# schematic.net
KiCad netlist of a schematic drawn in Altium Designer
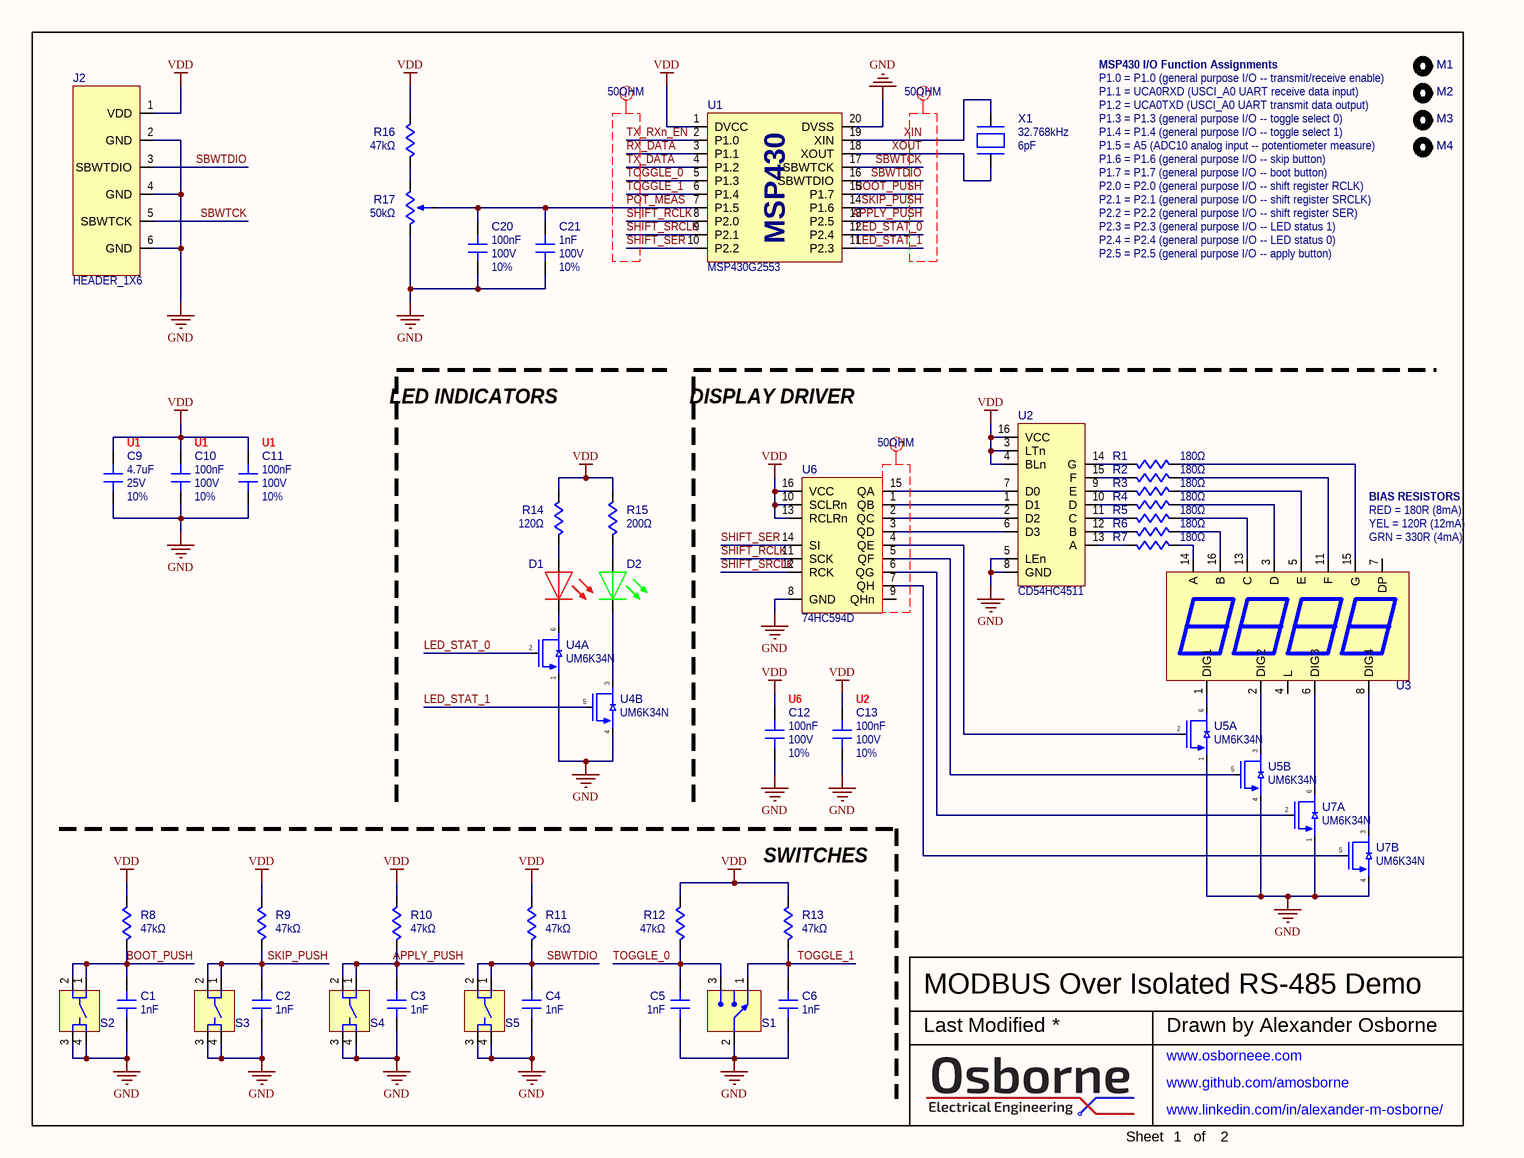
[diagram p0: schematic.SchDoc]

(export (version "E")
  (design (tool "Eeschema 10.0.6"))
  (components
    (comp (ref "C1")
      (value "1nF")
      (footprint "C0805")
      (description "CAP, CER, 1nF ±10%, 100V, 0805")
      (fields (field (name "VOLTAGE") "100V") (field (name "TOLERANCE") "10%"))
      (libsource (lib "schematic_library") (part "CAP-CER-1N00-10T-100V-0805"))
    )
    (comp (ref "C2")
      (value "1nF")
      (footprint "C0805")
      (description "CAP, CER, 1nF ±10%, 100V, 0805")
      (fields (field (name "VOLTAGE") "100V") (field (name "TOLERANCE") "10%"))
      (libsource (lib "schematic_library") (part "CAP-CER-1N00-10T-100V-0805"))
    )
    (comp (ref "C3")
      (value "1nF")
      (footprint "C0805")
      (description "CAP, CER, 1nF ±10%, 100V, 0805")
      (fields (field (name "VOLTAGE") "100V") (field (name "TOLERANCE") "10%"))
      (libsource (lib "schematic_library") (part "CAP-CER-1N00-10T-100V-0805"))
    )
    (comp (ref "C4")
      (value "1nF")
      (footprint "C0805")
      (description "CAP, CER, 1nF ±10%, 100V, 0805")
      (fields (field (name "VOLTAGE") "100V") (field (name "TOLERANCE") "10%"))
      (libsource (lib "schematic_library") (part "CAP-CER-1N00-10T-100V-0805"))
    )
    (comp (ref "C5")
      (value "1nF")
      (footprint "C0805")
      (description "CAP, CER, 1nF ±10%, 100V, 0805")
      (fields (field (name "VOLTAGE") "100V") (field (name "TOLERANCE") "10%"))
      (libsource (lib "schematic_library") (part "CAP-CER-1N00-10T-100V-0805"))
    )
    (comp (ref "C6")
      (value "1nF")
      (footprint "C0805")
      (description "CAP, CER, 1nF ±10%, 100V, 0805")
      (fields (field (name "VOLTAGE") "100V") (field (name "TOLERANCE") "10%"))
      (libsource (lib "schematic_library") (part "CAP-CER-1N00-10T-100V-0805"))
    )
    (comp (ref "C9")
      (value "4.7uF")
      (footprint "C0805")
      (description "CAP, CER, 4.7uF ±10%, 25V, 0805")
      (fields
        (field (name "VOLTAGE") "25V")
        (field (name "TOLERANCE") "10%")
        (field (name "Comment") "CAP-CER-4U70-10T-25V-0805")
      )
      (libsource (lib "schematic_library") (part "CAP-CER-4U70-10T-25V-0805"))
    )
    (comp (ref "C10")
      (value "100nF")
      (footprint "C0805")
      (description "CAP, CER, 100nF ±10%, 100V, 0805")
      (fields
        (field (name "VOLTAGE") "100V")
        (field (name "TOLERANCE") "10%")
        (field (name "Comment") "CAP-CER-100N-10T-100V-0805")
      )
      (libsource (lib "schematic_library") (part "CAP-CER-100N-10T-100V-0805"))
    )
    (comp (ref "C11")
      (value "100nF")
      (footprint "C0805")
      (description "CAP, CER, 100nF ±10%, 100V, 0805")
      (fields
        (field (name "VOLTAGE") "100V")
        (field (name "TOLERANCE") "10%")
        (field (name "Comment") "CAP-CER-100N-10T-100V-0805")
      )
      (libsource (lib "schematic_library") (part "CAP-CER-100N-10T-100V-0805"))
    )
    (comp (ref "C12")
      (value "100nF")
      (footprint "C0805")
      (description "CAP, CER, 100nF ±10%, 100V, 0805")
      (fields
        (field (name "VOLTAGE") "100V")
        (field (name "TOLERANCE") "10%")
        (field (name "Comment") "CAP-CER-100N-10T-100V-0805")
      )
      (libsource (lib "schematic_library") (part "CAP-CER-100N-10T-100V-0805"))
    )
    (comp (ref "C13")
      (value "100nF")
      (footprint "C0805")
      (description "CAP, CER, 100nF ±10%, 100V, 0805")
      (fields
        (field (name "VOLTAGE") "100V")
        (field (name "TOLERANCE") "10%")
        (field (name "Comment") "CAP-CER-100N-10T-100V-0805")
      )
      (libsource (lib "schematic_library") (part "CAP-CER-100N-10T-100V-0805"))
    )
    (comp (ref "C20")
      (value "100nF")
      (footprint "C0805")
      (description "CAP, CER, 100nF ±10%, 100V, 0805")
      (fields
        (field (name "VOLTAGE") "100V")
        (field (name "TOLERANCE") "10%")
        (field (name "Comment") "CAP-CER-100N-10T-100V-0805")
      )
      (libsource (lib "schematic_library") (part "CAP-CER-100N-10T-100V-0805"))
    )
    (comp (ref "C21")
      (value "1nF")
      (footprint "C0805")
      (description "CAP, CER, 1nF ±10%, 100V, 0805")
      (fields
        (field (name "VOLTAGE") "100V")
        (field (name "TOLERANCE") "10%")
        (field (name "Comment") "CAP-CER-1N00-10T-100V-0805")
      )
      (libsource (lib "schematic_library") (part "CAP-CER-1N00-10T-100V-0805"))
    )
    (comp (ref "D1")
      (value "LED_RED")
      (footprint "D0805")
      (description "Red LED Indicator 0805")
      (libsource (lib "schematic_library") (part "LED_RED"))
    )
    (comp (ref "D2")
      (value "LED_GREEN")
      (footprint "D0805")
      (description "Green LED Indicator 0805")
      (libsource (lib "schematic_library") (part "LED_GREEN"))
    )
    (comp (ref "J2")
      (value "HEADER_1X6")
      (footprint "Header_1x6")
      (description "Header, 1-Row, 6-Position")
      (libsource (lib "schematic_library") (part "HEADER_1X6"))
    )
    (comp (ref "M1")
      (value "MTG_HOLE")
      (footprint "MTG_HOLE_No4")
      (description "Mounting Hole")
      (libsource (lib "schematic_library") (part "MTG_HOLE"))
    )
    (comp (ref "M2")
      (value "MTG_HOLE")
      (footprint "MTG_HOLE_No4")
      (description "Mounting Hole")
      (libsource (lib "schematic_library") (part "MTG_HOLE"))
    )
    (comp (ref "M3")
      (value "MTG_HOLE")
      (footprint "MTG_HOLE_No4")
      (description "Mounting Hole")
      (libsource (lib "schematic_library") (part "MTG_HOLE"))
    )
    (comp (ref "M4")
      (value "MTG_HOLE")
      (footprint "MTG_HOLE_No4")
      (description "Mounting Hole")
      (libsource (lib "schematic_library") (part "MTG_HOLE"))
    )
    (comp (ref "R1")
      (value "180Ω")
      (footprint "R0805")
      (description "RES, 180Ω ±1.00%, 125mW, 0805")
      (fields (field (name "TOLERANCE") "1%") (field (name "POWER") "125mW"))
      (libsource (lib "schematic_library") (part "RES-180R-1T00-W125-0805"))
    )
    (comp (ref "R2")
      (value "180Ω")
      (footprint "R0805")
      (description "RES, 180Ω ±1.00%, 125mW, 0805")
      (fields (field (name "TOLERANCE") "1%") (field (name "POWER") "125mW"))
      (libsource (lib "schematic_library") (part "RES-180R-1T00-W125-0805"))
    )
    (comp (ref "R3")
      (value "180Ω")
      (footprint "R0805")
      (description "RES, 180Ω ±1.00%, 125mW, 0805")
      (fields (field (name "TOLERANCE") "1%") (field (name "POWER") "125mW"))
      (libsource (lib "schematic_library") (part "RES-180R-1T00-W125-0805"))
    )
    (comp (ref "R4")
      (value "180Ω")
      (footprint "R0805")
      (description "RES, 180Ω ±1.00%, 125mW, 0805")
      (fields (field (name "TOLERANCE") "1%") (field (name "POWER") "125mW"))
      (libsource (lib "schematic_library") (part "RES-180R-1T00-W125-0805"))
    )
    (comp (ref "R5")
      (value "180Ω")
      (footprint "R0805")
      (description "RES, 180Ω ±1.00%, 125mW, 0805")
      (fields (field (name "TOLERANCE") "1%") (field (name "POWER") "125mW"))
      (libsource (lib "schematic_library") (part "RES-180R-1T00-W125-0805"))
    )
    (comp (ref "R6")
      (value "180Ω")
      (footprint "R0805")
      (description "RES, 180Ω ±1.00%, 125mW, 0805")
      (fields (field (name "TOLERANCE") "1%") (field (name "POWER") "125mW"))
      (libsource (lib "schematic_library") (part "RES-180R-1T00-W125-0805"))
    )
    (comp (ref "R7")
      (value "180Ω")
      (footprint "R0805")
      (description "RES, 180Ω ±1.00%, 125mW, 0805")
      (fields (field (name "TOLERANCE") "1%") (field (name "POWER") "125mW"))
      (libsource (lib "schematic_library") (part "RES-180R-1T00-W125-0805"))
    )
    (comp (ref "R8")
      (value "47kΩ")
      (footprint "R0805")
      (description "RES, 47.0kΩ ±1.00%, 125mW, 0805")
      (fields (field (name "TOLERANCE") "1%") (field (name "POWER") "125mW"))
      (libsource (lib "schematic_library") (part "RES-47K0-1T00-W125-0805"))
    )
    (comp (ref "R9")
      (value "47kΩ")
      (footprint "R0805")
      (description "RES, 47.0kΩ ±1.00%, 125mW, 0805")
      (fields (field (name "TOLERANCE") "1%") (field (name "POWER") "125mW"))
      (libsource (lib "schematic_library") (part "RES-47K0-1T00-W125-0805"))
    )
    (comp (ref "R10")
      (value "47kΩ")
      (footprint "R0805")
      (description "RES, 47.0kΩ ±1.00%, 125mW, 0805")
      (fields (field (name "TOLERANCE") "1%") (field (name "POWER") "125mW"))
      (libsource (lib "schematic_library") (part "RES-47K0-1T00-W125-0805"))
    )
    (comp (ref "R11")
      (value "47kΩ")
      (footprint "R0805")
      (description "RES, 47.0kΩ ±1.00%, 125mW, 0805")
      (fields (field (name "TOLERANCE") "1%") (field (name "POWER") "125mW"))
      (libsource (lib "schematic_library") (part "RES-47K0-1T00-W125-0805"))
    )
    (comp (ref "R12")
      (value "47kΩ")
      (footprint "R0805")
      (description "RES, 47.0kΩ ±1.00%, 125mW, 0805")
      (fields (field (name "TOLERANCE") "1%") (field (name "POWER") "125mW"))
      (libsource (lib "schematic_library") (part "RES-47K0-1T00-W125-0805"))
    )
    (comp (ref "R13")
      (value "47kΩ")
      (footprint "R0805")
      (description "RES, 47.0kΩ ±1.00%, 125mW, 0805")
      (fields (field (name "TOLERANCE") "1%") (field (name "POWER") "125mW"))
      (libsource (lib "schematic_library") (part "RES-47K0-1T00-W125-0805"))
    )
    (comp (ref "R14")
      (value "120Ω")
      (footprint "R0805")
      (description "RES, 120Ω ±1.00%, 125mW, 0805")
      (fields (field (name "TOLERANCE") "1%") (field (name "POWER") "125mW"))
      (libsource (lib "schematic_library") (part "RES-120R-1T00-W125-0805"))
    )
    (comp (ref "R15")
      (value "200Ω")
      (footprint "R0805")
      (description "RES, 200Ω ±1.00%, 125mW, 0805")
      (fields (field (name "TOLERANCE") "1%") (field (name "POWER") "125mW"))
      (libsource (lib "schematic_library") (part "RES-200R-1T00-W125-0805"))
    )
    (comp (ref "R16")
      (value "47kΩ")
      (footprint "R0805")
      (description "RES, 47.0kΩ ±1.00%, 125mW, 0805")
      (fields (field (name "TOLERANCE") "1%") (field (name "POWER") "125mW"))
      (libsource (lib "schematic_library") (part "RES-47K0-1T00-W125-0805"))
    )
    (comp (ref "R17")
      (value "50kΩ")
      (footprint "3352T_Trimpot")
      (description "50kOhm Thumbwheel Potentiometer")
      (fields (field (name "Comment") "RES-50K0-TRIMMER"))
      (libsource (lib "schematic_library") (part "RES-50K0-TRIMMER"))
    )
    (comp (ref "S1")
      (value "SPDT-TOGGLE-SWITCH")
      (footprint "AST13SNCQ")
      (description "SPDT Toggle Switch, On-Off-On, Through Hole")
      (libsource (lib "schematic_library") (part "SPDT-TOGGLE-SWITCH"))
    )
    (comp (ref "S2")
      (value "PTS647")
      (footprint "PTS647")
      (description "PTS647 Series Tactile Switch")
      (libsource (lib "schematic_library") (part "PTS647"))
    )
    (comp (ref "S3")
      (value "PTS647")
      (footprint "PTS647")
      (description "PTS647 Series Tactile Switch")
      (libsource (lib "schematic_library") (part "PTS647"))
    )
    (comp (ref "S4")
      (value "PTS647")
      (footprint "PTS647")
      (description "PTS647 Series Tactile Switch")
      (libsource (lib "schematic_library") (part "PTS647"))
    )
    (comp (ref "S5")
      (value "PTS647")
      (footprint "PTS647")
      (description "PTS647 Series Tactile Switch")
      (libsource (lib "schematic_library") (part "PTS647"))
    )
    (comp (ref "U1")
      (value "MSP430G2553")
      (footprint "MSP430G2553_TSSOP-20")
      (description "MSP430 16-BIT, 16KB FLASH, 20-TSSOP")
      (libsource (lib "schematic_library") (part "MSP430G2553"))
    )
    (comp (ref "U2")
      (value "CD54HC4511")
      (footprint "CD54HC4511_SOIC-16")
      (description "BCD Decoder, 7-Segment Display Driver")
      (libsource (lib "schematic_library") (part "CD54HC4511"))
    )
    (comp (ref "U3")
      (value "QUAD-7SEG-DISP")
      (footprint "LTC-4727")
      (description "Quad 7-Segment Display, Common Cathode")
      (libsource (lib "schematic_library") (part "QUAD-7SEG-DISP"))
    )
    (comp (ref "U4")
      (value "UM6K34N")
      (footprint "UM6K34N_SC-88")
      (description "NCH+NCH 50V 200mA Small Signal MOSFET")
      (libsource (lib "schematic_library") (part "UM6K34N"))
    )
    (comp (ref "U5")
      (value "UM6K34N")
      (footprint "UM6K34N_SC-88")
      (description "NCH+NCH 50V 200mA Small Signal MOSFET")
      (libsource (lib "schematic_library") (part "UM6K34N"))
    )
    (comp (ref "U6")
      (value "74HC594D")
      (footprint "74HC594D_SOIC-16")
      (description "Shift Register, 8-Bit")
      (libsource (lib "schematic_library") (part "74HC594D"))
    )
    (comp (ref "U7")
      (value "UM6K34N")
      (footprint "UM6K34N_SC-88")
      (description "NCH+NCH 50V 200mA Small Signal MOSFET")
      (libsource (lib "schematic_library") (part "UM6K34N"))
    )
    (comp (ref "X1")
      (value "830014219B")
      (footprint "CRYSTAL_THT_2x6")
      (description "32.768kHz Tuning Fork Crystal, 6pF")
      (fields (field (name "CAPACITANCE") "6pF") (field (name "FREQUENCY") "32.768kHz"))
      (libsource (lib "schematic_library") (part "830014219B"))
    )
  )
  (nets
    (net (code "1") (name "/APPLY_PUSH") (class "Default")
      (node (ref "C3") (pin "1") (pintype "passive"))
      (node (ref "R10") (pin "2") (pintype "passive"))
      (node (ref "S4") (pin "1") (pintype "passive"))
      (node (ref "S4") (pin "2") (pintype "passive"))
      (node (ref "U1") (pin "13") (pinfunction "P2.5_13") (pintype "passive"))
    )
    (net (code "2") (name "/BOOT_PUSH") (class "Default")
      (node (ref "C1") (pin "1") (pintype "passive"))
      (node (ref "R8") (pin "2") (pintype "passive"))
      (node (ref "S2") (pin "1") (pintype "passive"))
      (node (ref "S2") (pin "2") (pintype "passive"))
      (node (ref "U1") (pin "15") (pinfunction "P1.7_15") (pintype "passive"))
    )
    (net (code "3") (name "/LED_STAT_0") (class "Default")
      (node (ref "U1") (pin "12") (pinfunction "P2.4_12") (pintype "passive"))
      (node (ref "U4") (pin "2") (pinfunction "G1_2") (pintype "passive"))
    )
    (net (code "4") (name "/LED_STAT_1") (class "Default")
      (node (ref "U1") (pin "11") (pinfunction "P2.3_11") (pintype "passive"))
      (node (ref "U4") (pin "5") (pinfunction "G2_5") (pintype "passive"))
    )
    (net (code "5") (name "/POT_MEAS") (class "Default")
      (node (ref "C20") (pin "1") (pintype "passive"))
      (node (ref "C21") (pin "1") (pintype "passive"))
      (node (ref "R17") (pin "2") (pintype "passive"))
      (node (ref "U1") (pin "7") (pinfunction "P1.5_7") (pintype "passive"))
    )
    (net (code "6") (name "/RX_DATA") (class "Default")
      (node (ref "U1") (pin "3") (pinfunction "P1.1_3") (pintype "passive"))
    )
    (net (code "7") (name "/SBWTCK") (class "Default")
      (node (ref "J2") (pin "5") (pinfunction "SBWTCK_5") (pintype "passive"))
      (node (ref "U1") (pin "17") (pinfunction "SBWTCK_17") (pintype "passive"))
    )
    (net (code "8") (name "/SBWTDIO") (class "Default")
      (node (ref "C4") (pin "1") (pintype "passive"))
      (node (ref "J2") (pin "3") (pinfunction "SBWTDIO_3") (pintype "passive"))
      (node (ref "R11") (pin "2") (pintype "passive"))
      (node (ref "S5") (pin "1") (pintype "passive"))
      (node (ref "S5") (pin "2") (pintype "passive"))
      (node (ref "U1") (pin "16") (pinfunction "SBWTDIO_16") (pintype "passive"))
    )
    (net (code "9") (name "/SHIFT_RCLK") (class "Default")
      (node (ref "U1") (pin "8") (pinfunction "P2.0_8") (pintype "passive"))
      (node (ref "U6") (pin "11") (pinfunction "SCK_11") (pintype "passive"))
    )
    (net (code "10") (name "/SHIFT_SER") (class "Default")
      (node (ref "U1") (pin "10") (pinfunction "P2.2_10") (pintype "passive"))
      (node (ref "U6") (pin "14") (pinfunction "SI_14") (pintype "passive"))
    )
    (net (code "11") (name "/SHIFT_SRCLK") (class "Default")
      (node (ref "U1") (pin "9") (pinfunction "P2.1_9") (pintype "passive"))
      (node (ref "U6") (pin "12") (pinfunction "RCK_12") (pintype "passive"))
    )
    (net (code "12") (name "/SKIP_PUSH") (class "Default")
      (node (ref "C2") (pin "1") (pintype "passive"))
      (node (ref "R9") (pin "2") (pintype "passive"))
      (node (ref "S3") (pin "1") (pintype "passive"))
      (node (ref "S3") (pin "2") (pintype "passive"))
      (node (ref "U1") (pin "14") (pinfunction "P1.6_14") (pintype "passive"))
    )
    (net (code "13") (name "/TOGGLE_0") (class "Default")
      (node (ref "C5") (pin "1") (pintype "passive"))
      (node (ref "R12") (pin "2") (pintype "passive"))
      (node (ref "S1") (pin "3") (pintype "passive"))
      (node (ref "U1") (pin "5") (pinfunction "P1.3_5") (pintype "passive"))
    )
    (net (code "14") (name "/TOGGLE_1") (class "Default")
      (node (ref "C6") (pin "1") (pintype "passive"))
      (node (ref "R13") (pin "2") (pintype "passive"))
      (node (ref "S1") (pin "1") (pintype "passive"))
      (node (ref "U1") (pin "6") (pinfunction "P1.4_6") (pintype "passive"))
    )
    (net (code "15") (name "/TX_DATA") (class "Default")
      (node (ref "U1") (pin "4") (pinfunction "P1.2_4") (pintype "passive"))
    )
    (net (code "16") (name "/TX_RXn_EN") (class "Default")
      (node (ref "U1") (pin "2") (pinfunction "P1.0_2") (pintype "passive"))
    )
    (net (code "17") (name "/XIN") (class "Default")
      (node (ref "U1") (pin "19") (pinfunction "XIN_19") (pintype "passive"))
      (node (ref "X1") (pin "1") (pinfunction "1_1") (pintype "passive"))
    )
    (net (code "18") (name "/XOUT") (class "Default")
      (node (ref "U1") (pin "18") (pinfunction "XOUT_18") (pintype "passive"))
      (node (ref "X1") (pin "2") (pinfunction "2_2") (pintype "passive"))
    )
    (net (code "19") (name "GND") (class "Default")
      (node (ref "C1") (pin "2") (pintype "passive"))
      (node (ref "C10") (pin "2") (pintype "passive"))
      (node (ref "C11") (pin "2") (pintype "passive"))
      (node (ref "C12") (pin "2") (pintype "passive"))
      (node (ref "C13") (pin "2") (pintype "passive"))
      (node (ref "C2") (pin "2") (pintype "passive"))
      (node (ref "C20") (pin "2") (pintype "passive"))
      (node (ref "C21") (pin "2") (pintype "passive"))
      (node (ref "C3") (pin "2") (pintype "passive"))
      (node (ref "C4") (pin "2") (pintype "passive"))
      (node (ref "C5") (pin "2") (pintype "passive"))
      (node (ref "C6") (pin "2") (pintype "passive"))
      (node (ref "C9") (pin "2") (pintype "passive"))
      (node (ref "J2") (pin "2") (pinfunction "GND_2") (pintype "passive"))
      (node (ref "J2") (pin "4") (pinfunction "GND_4") (pintype "passive"))
      (node (ref "J2") (pin "6") (pinfunction "GND_6") (pintype "passive"))
      (node (ref "R17") (pin "3") (pintype "passive"))
      (node (ref "S1") (pin "2") (pintype "passive"))
      (node (ref "S2") (pin "3") (pintype "passive"))
      (node (ref "S2") (pin "4") (pintype "passive"))
      (node (ref "S3") (pin "3") (pintype "passive"))
      (node (ref "S3") (pin "4") (pintype "passive"))
      (node (ref "S4") (pin "3") (pintype "passive"))
      (node (ref "S4") (pin "4") (pintype "passive"))
      (node (ref "S5") (pin "3") (pintype "passive"))
      (node (ref "S5") (pin "4") (pintype "passive"))
      (node (ref "U1") (pin "20") (pinfunction "DVSS_20") (pintype "passive"))
      (node (ref "U2") (pin "5") (pinfunction "LEn_5") (pintype "passive"))
      (node (ref "U2") (pin "8") (pinfunction "GND_8") (pintype "passive"))
      (node (ref "U4") (pin "1") (pinfunction "S1_1") (pintype "passive"))
      (node (ref "U4") (pin "4") (pinfunction "S2_4") (pintype "passive"))
      (node (ref "U5") (pin "1") (pinfunction "S1_1") (pintype "passive"))
      (node (ref "U5") (pin "4") (pinfunction "S2_4") (pintype "passive"))
      (node (ref "U6") (pin "8") (pinfunction "GND_8") (pintype "passive"))
      (node (ref "U7") (pin "1") (pinfunction "S1_1") (pintype "passive"))
      (node (ref "U7") (pin "4") (pinfunction "S2_4") (pintype "passive"))
    )
    (net (code "20") (name "Net-(D1-Pad2)") (class "Default")
      (node (ref "D1") (pin "2") (pinfunction "2_2") (pintype "passive"))
      (node (ref "R14") (pin "2") (pintype "passive"))
    )
    (net (code "21") (name "Net-(D2-Pad2)") (class "Default")
      (node (ref "D2") (pin "2") (pinfunction "2_2") (pintype "passive"))
      (node (ref "R15") (pin "2") (pintype "passive"))
    )
    (net (code "22") (name "Net-(R16-Pad2)") (class "Default")
      (node (ref "R16") (pin "2") (pintype "passive"))
      (node (ref "R17") (pin "1") (pintype "passive"))
    )
    (net (code "23") (name "Net-(U2-A)") (class "Default")
      (node (ref "R7") (pin "1") (pintype "passive"))
      (node (ref "U2") (pin "13") (pinfunction "A_13") (pintype "passive"))
    )
    (net (code "24") (name "Net-(U2-B)") (class "Default")
      (node (ref "R6") (pin "1") (pintype "passive"))
      (node (ref "U2") (pin "12") (pinfunction "B_12") (pintype "passive"))
    )
    (net (code "25") (name "Net-(U2-C)") (class "Default")
      (node (ref "R5") (pin "1") (pintype "passive"))
      (node (ref "U2") (pin "11") (pinfunction "C_11") (pintype "passive"))
    )
    (net (code "26") (name "Net-(U2-D)") (class "Default")
      (node (ref "R4") (pin "1") (pintype "passive"))
      (node (ref "U2") (pin "10") (pinfunction "D_10") (pintype "passive"))
    )
    (net (code "27") (name "Net-(U2-D0)") (class "Default")
      (node (ref "U2") (pin "7") (pinfunction "D0_7") (pintype "passive"))
      (node (ref "U6") (pin "15") (pinfunction "QA_15") (pintype "passive"))
    )
    (net (code "28") (name "Net-(U2-D1)") (class "Default")
      (node (ref "U2") (pin "1") (pinfunction "D1_1") (pintype "passive"))
      (node (ref "U6") (pin "1") (pinfunction "QB_1") (pintype "passive"))
    )
    (net (code "29") (name "Net-(U2-D2)") (class "Default")
      (node (ref "U2") (pin "2") (pinfunction "D2_2") (pintype "passive"))
      (node (ref "U6") (pin "2") (pinfunction "QC_2") (pintype "passive"))
    )
    (net (code "30") (name "Net-(U2-D3)") (class "Default")
      (node (ref "U2") (pin "6") (pinfunction "D3_6") (pintype "passive"))
      (node (ref "U6") (pin "3") (pinfunction "QD_3") (pintype "passive"))
    )
    (net (code "31") (name "Net-(U2-E)") (class "Default")
      (node (ref "R3") (pin "1") (pintype "passive"))
      (node (ref "U2") (pin "9") (pinfunction "E_9") (pintype "passive"))
    )
    (net (code "32") (name "Net-(U2-F)") (class "Default")
      (node (ref "R2") (pin "1") (pintype "passive"))
      (node (ref "U2") (pin "15") (pinfunction "F_15") (pintype "passive"))
    )
    (net (code "33") (name "Net-(U2-G)") (class "Default")
      (node (ref "R1") (pin "1") (pintype "passive"))
      (node (ref "U2") (pin "14") (pinfunction "G_14") (pintype "passive"))
    )
    (net (code "34") (name "Net-(U3-A)") (class "Default")
      (node (ref "R7") (pin "2") (pintype "passive"))
      (node (ref "U3") (pin "14") (pinfunction "A_14") (pintype "passive"))
    )
    (net (code "35") (name "Net-(U3-B)") (class "Default")
      (node (ref "R6") (pin "2") (pintype "passive"))
      (node (ref "U3") (pin "16") (pinfunction "B_16") (pintype "passive"))
    )
    (net (code "36") (name "Net-(U3-C)") (class "Default")
      (node (ref "R5") (pin "2") (pintype "passive"))
      (node (ref "U3") (pin "13") (pinfunction "C_13") (pintype "passive"))
    )
    (net (code "37") (name "Net-(U3-D)") (class "Default")
      (node (ref "R4") (pin "2") (pintype "passive"))
      (node (ref "U3") (pin "3") (pinfunction "D_3") (pintype "passive"))
    )
    (net (code "38") (name "Net-(U3-DIG1)") (class "Default")
      (node (ref "U3") (pin "1") (pinfunction "DIG1_1") (pintype "passive"))
      (node (ref "U5") (pin "6") (pinfunction "D1_6") (pintype "passive"))
    )
    (net (code "39") (name "Net-(U3-DIG2)") (class "Default")
      (node (ref "U3") (pin "2") (pinfunction "DIG2_2") (pintype "passive"))
      (node (ref "U5") (pin "3") (pinfunction "D2_3") (pintype "passive"))
    )
    (net (code "40") (name "Net-(U3-DIG3)") (class "Default")
      (node (ref "U3") (pin "6") (pinfunction "DIG3_6") (pintype "passive"))
      (node (ref "U7") (pin "6") (pinfunction "D1_6") (pintype "passive"))
    )
    (net (code "41") (name "Net-(U3-DIG4)") (class "Default")
      (node (ref "U3") (pin "8") (pinfunction "DIG4_8") (pintype "passive"))
      (node (ref "U7") (pin "3") (pinfunction "D2_3") (pintype "passive"))
    )
    (net (code "42") (name "Net-(U3-E)") (class "Default")
      (node (ref "R3") (pin "2") (pintype "passive"))
      (node (ref "U3") (pin "5") (pinfunction "E_5") (pintype "passive"))
    )
    (net (code "43") (name "Net-(U3-F)") (class "Default")
      (node (ref "R2") (pin "2") (pintype "passive"))
      (node (ref "U3") (pin "11") (pinfunction "F_11") (pintype "passive"))
    )
    (net (code "44") (name "Net-(U3-G)") (class "Default")
      (node (ref "R1") (pin "2") (pintype "passive"))
      (node (ref "U3") (pin "15") (pinfunction "G_15") (pintype "passive"))
    )
    (net (code "45") (name "Net-(U4A-D1)") (class "Default")
      (node (ref "D1") (pin "1") (pinfunction "1_1") (pintype "passive"))
      (node (ref "U4") (pin "6") (pinfunction "D1_6") (pintype "passive"))
    )
    (net (code "46") (name "Net-(U4B-D2)") (class "Default")
      (node (ref "D2") (pin "1") (pinfunction "1_1") (pintype "passive"))
      (node (ref "U4") (pin "3") (pinfunction "D2_3") (pintype "passive"))
    )
    (net (code "47") (name "Net-(U5A-G1)") (class "Default")
      (node (ref "U5") (pin "2") (pinfunction "G1_2") (pintype "passive"))
      (node (ref "U6") (pin "4") (pinfunction "QE_4") (pintype "passive"))
    )
    (net (code "48") (name "Net-(U5B-G2)") (class "Default")
      (node (ref "U5") (pin "5") (pinfunction "G2_5") (pintype "passive"))
      (node (ref "U6") (pin "5") (pinfunction "QF_5") (pintype "passive"))
    )
    (net (code "49") (name "Net-(U6-QG)") (class "Default")
      (node (ref "U6") (pin "6") (pinfunction "QG_6") (pintype "passive"))
      (node (ref "U7") (pin "2") (pinfunction "G1_2") (pintype "passive"))
    )
    (net (code "50") (name "Net-(U6-QH)") (class "Default")
      (node (ref "U6") (pin "7") (pinfunction "QH_7") (pintype "passive"))
      (node (ref "U7") (pin "5") (pinfunction "G2_5") (pintype "passive"))
    )
    (net (code "51") (name "VDD") (class "Default")
      (node (ref "C10") (pin "1") (pintype "passive"))
      (node (ref "C11") (pin "1") (pintype "passive"))
      (node (ref "C12") (pin "1") (pintype "passive"))
      (node (ref "C13") (pin "1") (pintype "passive"))
      (node (ref "C9") (pin "1") (pintype "passive"))
      (node (ref "J2") (pin "1") (pinfunction "VDD_1") (pintype "passive"))
      (node (ref "R10") (pin "1") (pintype "passive"))
      (node (ref "R11") (pin "1") (pintype "passive"))
      (node (ref "R12") (pin "1") (pintype "passive"))
      (node (ref "R13") (pin "1") (pintype "passive"))
      (node (ref "R14") (pin "1") (pintype "passive"))
      (node (ref "R15") (pin "1") (pintype "passive"))
      (node (ref "R16") (pin "1") (pintype "passive"))
      (node (ref "R8") (pin "1") (pintype "passive"))
      (node (ref "R9") (pin "1") (pintype "passive"))
      (node (ref "U1") (pin "1") (pinfunction "DVCC_1") (pintype "passive"))
      (node (ref "U2") (pin "16") (pinfunction "VCC_16") (pintype "passive"))
      (node (ref "U2") (pin "3") (pinfunction "LTn_3") (pintype "passive"))
      (node (ref "U2") (pin "4") (pinfunction "BLn_4") (pintype "passive"))
      (node (ref "U6") (pin "10") (pinfunction "SCLRn_10") (pintype "passive"))
      (node (ref "U6") (pin "13") (pinfunction "RCLRn_13") (pintype "passive"))
      (node (ref "U6") (pin "16") (pinfunction "VCC_16") (pintype "passive"))
    )
    (net (code "52") (name "unconnected-(U3-DP-Pad7)") (class "Default")
      (node (ref "U3") (pin "7") (pinfunction "DP_7") (pintype "passive"))
    )
    (net (code "53") (name "unconnected-(U3-L-Pad4)") (class "Default")
      (node (ref "U3") (pin "4") (pinfunction "L_4") (pintype "passive"))
    )
    (net (code "54") (name "unconnected-(U3-NC-Pad9)") (class "Default")
      (node (ref "U3") (pin "9") (pinfunction "NC_9") (pintype "passive"))
    )
    (net (code "55") (name "unconnected-(U6-QHn-Pad9)") (class "Default")
      (node (ref "U6") (pin "9") (pinfunction "QHn_9") (pintype "passive"))
    )
  )
)
